# TMP75.net
KiCad netlist of a schematic drawn in Altium Designer
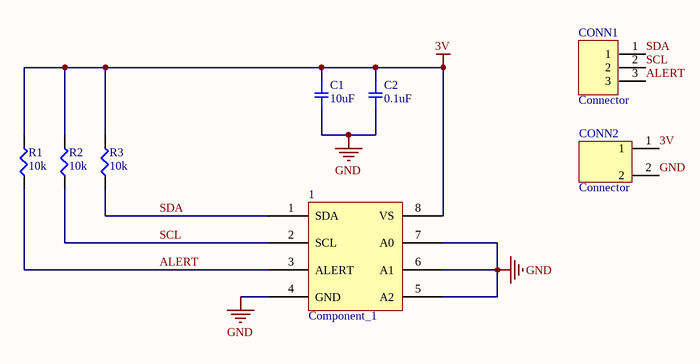
[diagram p0: TMP75.SchDoc]

(export (version "E")
  (design (tool "Eeschema 10.0.6"))
  (components
    (comp (ref "1")
      (value "Component_1")
      (footprint "TMP75C")
      (libsource (lib "TMP75C") (part "Component_1"))
    )
    (comp (ref "C1")
      (value "10uF")
      (footprint "SMD-0805C")
      (description "Cap Ceramic 10uF 25V X5R 10% 0805")
      (fields
        (field (name "PART NUMBER") "CL21A106KAFN3NE")
        (field (name "MANUFACTURER") "Samsung Electro-Mechanics")
      )
      (libsource (lib "capacitor_0805") (part "CL21A106KAFN3NE"))
    )
    (comp (ref "C2")
      (value "0.1uF")
      (footprint "SMD-0805C")
      (description "CAP CER 0.1uF 50V X7T 0805")
      (fields
        (field (name "PART NUMBER") "GC321AD72E103KX01D")
        (field (name "MANUFACTURER") "Samsung Electro-Mechanics")
      )
      (libsource (lib "capacitor_0805") (part "CL21B104JBCNNNC"))
    )
    (comp (ref "CONN1")
      (value "Connector")
      (footprint "1x3x2.54 Pin Header TH V")
      (libsource (lib "Connectors") (part "Header 1x3"))
    )
    (comp (ref "CONN2")
      (value "Connector")
      (footprint "1x2x2.54 Pin Header TH V")
      (libsource (lib "Connectors") (part "Header 1x2"))
    )
    (comp (ref "R1")
      (value "10k")
      (footprint "SMD-0805-RES")
      (description "RES SMD 10K OHM 5% 1/2W 0805")
      (fields (field (name "PART NUMBER") "ERJ-P6WJ103V") (field (name "DIGI-KEY PART NUMBER") "P16966CT-ND"))
      (libsource (lib "Panasonic_ERJ_0805") (part "ERJ-P6WJ103V"))
    )
    (comp (ref "R2")
      (value "10k")
      (footprint "SMD-0805-RES")
      (description "RES SMD 10K OHM 5% 1/2W 0805")
      (fields (field (name "PART NUMBER") "ERJ-P6WJ103V") (field (name "DIGI-KEY PART NUMBER") "P16966CT-ND"))
      (libsource (lib "Panasonic_ERJ_0805") (part "ERJ-P6WJ103V"))
    )
    (comp (ref "R3")
      (value "10k")
      (footprint "SMD-0805-RES")
      (description "RES SMD 10K OHM 5% 1/2W 0805")
      (fields (field (name "PART NUMBER") "ERJ-P6WJ103V") (field (name "DIGI-KEY PART NUMBER") "P16966CT-ND"))
      (libsource (lib "Panasonic_ERJ_0805") (part "ERJ-P6WJ103V"))
    )
  )
  (nets
    (net (code "1") (name "/ALERT") (class "Default")
      (node (ref "1") (pin "3") (pinfunction "ALERT_3") (pintype "passive"))
      (node (ref "CONN1") (pin "3") (pinfunction "3_3") (pintype "passive"))
      (node (ref "R1") (pin "1") (pinfunction "1_1") (pintype "passive"))
    )
    (net (code "2") (name "/SCL") (class "Default")
      (node (ref "1") (pin "2") (pinfunction "SCL_2") (pintype "passive"))
      (node (ref "CONN1") (pin "2") (pinfunction "2_2") (pintype "passive"))
      (node (ref "R2") (pin "1") (pinfunction "1_1") (pintype "passive"))
    )
    (net (code "3") (name "/SDA") (class "Default")
      (node (ref "1") (pin "1") (pinfunction "SDA_1") (pintype "passive"))
      (node (ref "CONN1") (pin "1") (pinfunction "1_1") (pintype "passive"))
      (node (ref "R3") (pin "1") (pinfunction "1_1") (pintype "passive"))
    )
    (net (code "4") (name "3V") (class "Default")
      (node (ref "1") (pin "8") (pinfunction "VS_8") (pintype "passive"))
      (node (ref "C1") (pin "1") (pinfunction "1_1") (pintype "passive"))
      (node (ref "C2") (pin "1") (pinfunction "1_1") (pintype "passive"))
      (node (ref "CONN2") (pin "1") (pinfunction "1_1") (pintype "passive"))
      (node (ref "R1") (pin "2") (pinfunction "2_2") (pintype "passive"))
      (node (ref "R2") (pin "2") (pinfunction "2_2") (pintype "passive"))
      (node (ref "R3") (pin "2") (pinfunction "2_2") (pintype "passive"))
    )
    (net (code "5") (name "GND") (class "Default")
      (node (ref "1") (pin "4") (pinfunction "GND_4") (pintype "passive"))
      (node (ref "1") (pin "5") (pinfunction "A2_5") (pintype "passive"))
      (node (ref "1") (pin "6") (pinfunction "A1_6") (pintype "passive"))
      (node (ref "1") (pin "7") (pinfunction "A0_7") (pintype "passive"))
      (node (ref "C1") (pin "2") (pinfunction "2_2") (pintype "passive"))
      (node (ref "C2") (pin "2") (pinfunction "2_2") (pintype "passive"))
      (node (ref "CONN2") (pin "2") (pinfunction "2_2") (pintype "passive"))
    )
  )
)
